# LB_BIT_i18_MOTIONTRIGGER-v03_rev1.net
KiCad netlist of a schematic drawn in EAGLE
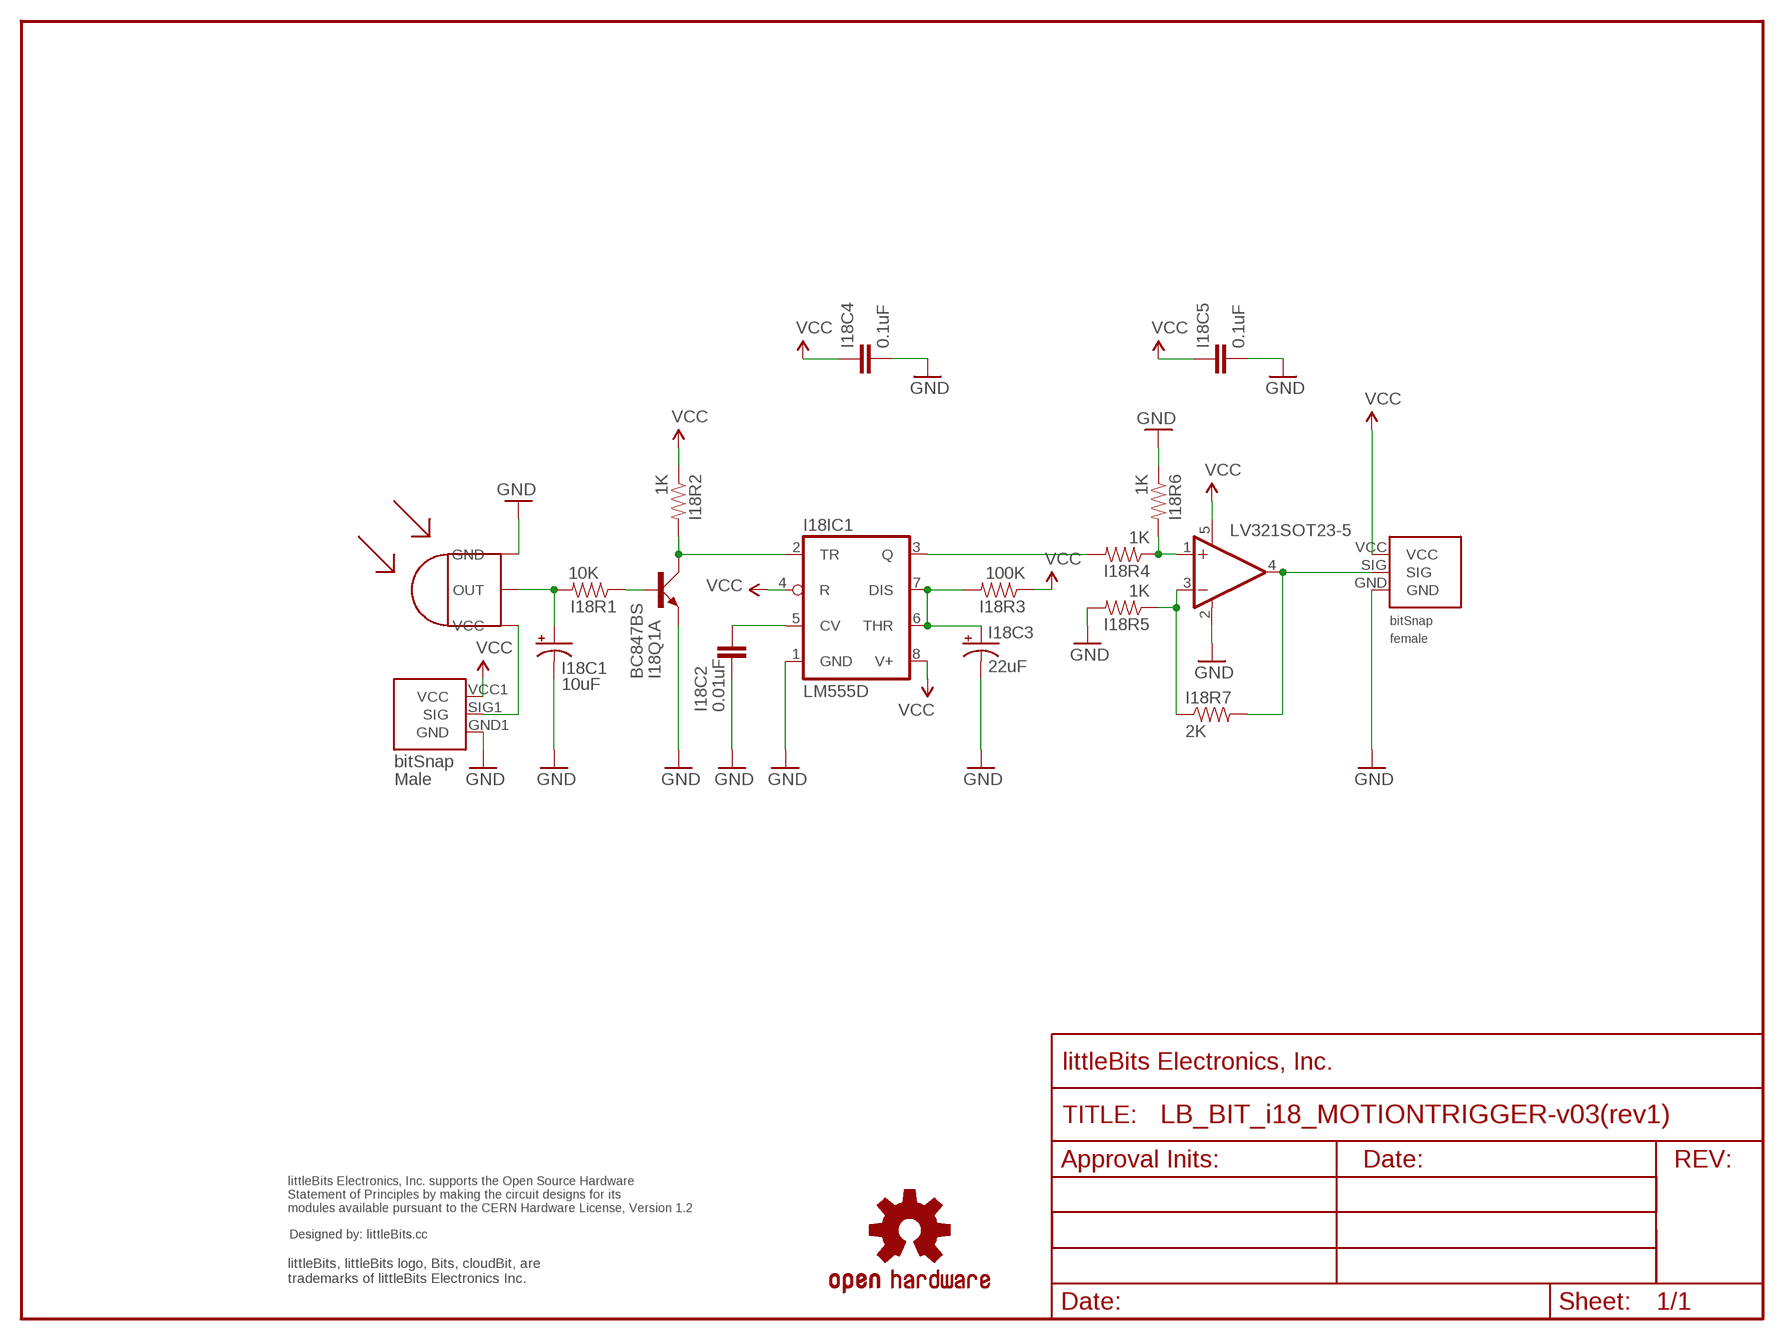
[diagram p0: schematic, sheet 1]

(export (version "E")
  (design (tool "Eeschema 10.0.6"))
  (components
    (comp (ref "I18BSF")
      (value "BITSNAP_V03_FEMALE")
      (footprint "eagle-import:BITSNAP_V03_FEMALE")
      (libsource (lib "eagle-import") (part "BITSNAP_V03_FEMALE"))
    )
    (comp (ref "I18BSM")
      (value "BITSNAP_V03_MALE")
      (footprint "eagle-import:BITSNAP_V03_MALE")
      (libsource (lib "eagle-import") (part "BITSNAP_V03_MALE"))
    )
    (comp (ref "I18C1")
      (value "10uF")
      (footprint "eagle-import:EIA3216")
      (libsource (lib "eagle-import") (part "CAP_POL1206"))
    )
    (comp (ref "I18C2")
      (value "0.01uF")
      (footprint "eagle-import:0603-CAP")
      (libsource (lib "eagle-import") (part "CAP0603-CAP"))
    )
    (comp (ref "I18C3")
      (value "22uF")
      (footprint "eagle-import:EIA3216")
      (libsource (lib "eagle-import") (part "CAP_POL1206"))
    )
    (comp (ref "I18C4")
      (value "0.1uF")
      (footprint "eagle-import:0603-CAP")
      (libsource (lib "eagle-import") (part "CAP0603-CAP"))
    )
    (comp (ref "I18C5")
      (value "0.1uF")
      (footprint "eagle-import:0603-CAP")
      (libsource (lib "eagle-import") (part "CAP0603-CAP"))
    )
    (comp (ref "I18IC1")
      (value "LM555D")
      (footprint "eagle-import:SO08")
      (libsource (lib "eagle-import") (part "555DLM"))
    )
    (comp (ref "I18Q1")
      (value "BC847BS")
      (footprint "eagle-import:SOT363_PHILIPS")
      (libsource (lib "eagle-import") (part "BC847BS"))
    )
    (comp (ref "I18R1")
      (value "10K")
      (footprint "eagle-import:0603-RES")
      (libsource (lib "eagle-import") (part "RESISTOR0603-RES"))
    )
    (comp (ref "I18R2")
      (value "1K")
      (footprint "eagle-import:0603-RES")
      (libsource (lib "eagle-import") (part "RESISTOR0603-RES"))
    )
    (comp (ref "I18R3")
      (value "100K")
      (footprint "eagle-import:0603-RES")
      (libsource (lib "eagle-import") (part "RESISTOR0603-RES"))
    )
    (comp (ref "I18R4")
      (value "1K")
      (footprint "eagle-import:0603-RES")
      (libsource (lib "eagle-import") (part "RESISTOR0603-RES"))
    )
    (comp (ref "I18R5")
      (value "1K")
      (footprint "eagle-import:0603-RES")
      (libsource (lib "eagle-import") (part "RESISTOR0603-RES"))
    )
    (comp (ref "I18R6")
      (value "1K")
      (footprint "eagle-import:0603-RES")
      (libsource (lib "eagle-import") (part "RESISTOR0603-RES"))
    )
    (comp (ref "I18R7")
      (value "2K")
      (footprint "eagle-import:0603-RES")
      (libsource (lib "eagle-import") (part "RESISTOR0603-RES"))
    )
    (comp (ref "I18U1")
      (value "PIR-EKMC1601112")
      (footprint "eagle-import:PIR-EKMC1601112")
      (libsource (lib "eagle-import") (part "PIR-EKMC1601112"))
    )
    (comp (ref "I18U2")
      (value "LV321SOT23-5")
      (footprint "eagle-import:SOT23-5")
      (libsource (lib "eagle-import") (part "LV321SOT23-5"))
    )
    (comp (ref "U$1")
      (value "OSHWCREDIT")
      (footprint "eagle-import:OSHWCREDIT")
      (libsource (lib "eagle-import") (part "OSHWCREDIT"))
    )
    (comp (ref "U$2")
      (value "FRAME-LETTER-OHWOHW")
      (footprint "eagle-import:FABDWG01-OHW")
      (libsource (lib "eagle-import") (part "FRAME-LETTER-OHWOHW"))
    )
    (comp (ref "U$8")
      (value "OSHW-LOGOL")
      (footprint "eagle-import:OSHW-LOGO-L")
      (libsource (lib "eagle-import") (part "OSHW-LOGOL"))
    )
  )
  (nets
    (net (code "1") (name "GND") (class "Default")
      (node (ref "I18BSF") (pin "GND") (pinfunction "GND_GND") (pintype "bidirectional"))
      (node (ref "I18BSM") (pin "GND1") (pinfunction "GND_GND1") (pintype "bidirectional"))
      (node (ref "I18C1") (pin "C") (pinfunction "-_C") (pintype "passive"))
      (node (ref "I18C2") (pin "2") (pinfunction "2_2") (pintype "passive"))
      (node (ref "I18C3") (pin "C") (pinfunction "-_C") (pintype "passive"))
      (node (ref "I18C4") (pin "2") (pinfunction "2_2") (pintype "passive"))
      (node (ref "I18C5") (pin "2") (pinfunction "2_2") (pintype "passive"))
      (node (ref "I18IC1") (pin "1") (pinfunction "GND_1") (pintype "power_in"))
      (node (ref "I18Q1") (pin "1") (pinfunction "E_1") (pintype "passive"))
      (node (ref "I18R5") (pin "2") (pinfunction "2_2") (pintype "passive"))
      (node (ref "I18R6") (pin "1") (pinfunction "1_1") (pintype "passive"))
      (node (ref "I18U1") (pin "GND") (pinfunction "GND_GND") (pintype "bidirectional"))
      (node (ref "I18U2") (pin "2") (pinfunction "V-_2") (pintype "power_in"))
    )
    (net (code "2") (name "Net-(I18BSM-SIG)") (class "Default")
      (node (ref "I18BSM") (pin "SIG1") (pinfunction "SIG_SIG1") (pintype "bidirectional"))
      (node (ref "I18U1") (pin "VCC") (pinfunction "VCC_VCC") (pintype "bidirectional"))
    )
    (net (code "3") (name "Net-(I18C1-+)") (class "Default")
      (node (ref "I18C1") (pin "A") (pinfunction "+_A") (pintype "passive"))
      (node (ref "I18R1") (pin "2") (pinfunction "2_2") (pintype "passive"))
      (node (ref "I18U1") (pin "OUT") (pinfunction "OUT_OUT") (pintype "bidirectional"))
    )
    (net (code "4") (name "Net-(I18C3-+)") (class "Default")
      (node (ref "I18C3") (pin "A") (pinfunction "+_A") (pintype "passive"))
      (node (ref "I18IC1") (pin "6") (pinfunction "THR_6") (pintype "input"))
      (node (ref "I18IC1") (pin "7") (pinfunction "DIS_7") (pintype "input"))
      (node (ref "I18R3") (pin "2") (pinfunction "2_2") (pintype "passive"))
    )
    (net (code "5") (name "Net-(I18IC1-CV)") (class "Default")
      (node (ref "I18C2") (pin "1") (pinfunction "1_1") (pintype "passive"))
      (node (ref "I18IC1") (pin "5") (pinfunction "CV_5") (pintype "input"))
    )
    (net (code "6") (name "Net-(I18IC1-Q)") (class "Default")
      (node (ref "I18IC1") (pin "3") (pinfunction "Q_3") (pintype "output"))
      (node (ref "I18R4") (pin "2") (pinfunction "2_2") (pintype "passive"))
    )
    (net (code "7") (name "Net-(I18IC1-TR)") (class "Default")
      (node (ref "I18IC1") (pin "2") (pinfunction "TR_2") (pintype "input"))
      (node (ref "I18Q1") (pin "6") (pinfunction "C_6") (pintype "passive"))
      (node (ref "I18R2") (pin "2") (pinfunction "2_2") (pintype "passive"))
    )
    (net (code "8") (name "Net-(I18Q1A-B)") (class "Default")
      (node (ref "I18Q1") (pin "2") (pinfunction "B_2") (pintype "passive"))
      (node (ref "I18R1") (pin "1") (pinfunction "1_1") (pintype "passive"))
    )
    (net (code "9") (name "Net-(I18U2-+IN)") (class "Default")
      (node (ref "I18R4") (pin "1") (pinfunction "1_1") (pintype "passive"))
      (node (ref "I18R6") (pin "2") (pinfunction "2_2") (pintype "passive"))
      (node (ref "I18U2") (pin "1") (pinfunction "+IN_1") (pintype "input"))
    )
    (net (code "10") (name "Net-(I18U2--IN)") (class "Default")
      (node (ref "I18R5") (pin "1") (pinfunction "1_1") (pintype "passive"))
      (node (ref "I18R7") (pin "1") (pinfunction "1_1") (pintype "passive"))
      (node (ref "I18U2") (pin "3") (pinfunction "-IN_3") (pintype "input"))
    )
    (net (code "11") (name "Net-(I18U2-OUT)") (class "Default")
      (node (ref "I18BSF") (pin "SIG") (pinfunction "SIG_SIG") (pintype "bidirectional"))
      (node (ref "I18R7") (pin "2") (pinfunction "2_2") (pintype "passive"))
      (node (ref "I18U2") (pin "4") (pinfunction "OUT_4") (pintype "output"))
    )
    (net (code "12") (name "VCC") (class "Default")
      (node (ref "I18BSF") (pin "VCC") (pinfunction "VCC_VCC") (pintype "bidirectional"))
      (node (ref "I18BSM") (pin "VCC1") (pinfunction "VCC_VCC1") (pintype "bidirectional"))
      (node (ref "I18C4") (pin "1") (pinfunction "1_1") (pintype "passive"))
      (node (ref "I18C5") (pin "1") (pinfunction "1_1") (pintype "passive"))
      (node (ref "I18IC1") (pin "4") (pinfunction "R_4") (pintype "input"))
      (node (ref "I18IC1") (pin "8") (pinfunction "V+_8") (pintype "power_in"))
      (node (ref "I18R2") (pin "1") (pinfunction "1_1") (pintype "passive"))
      (node (ref "I18R3") (pin "1") (pinfunction "1_1") (pintype "passive"))
      (node (ref "I18U2") (pin "5") (pinfunction "V+_5") (pintype "power_in"))
    )
  )
)
